# 0_Overview.net
KiCad netlist of a schematic drawn in Altium Designer
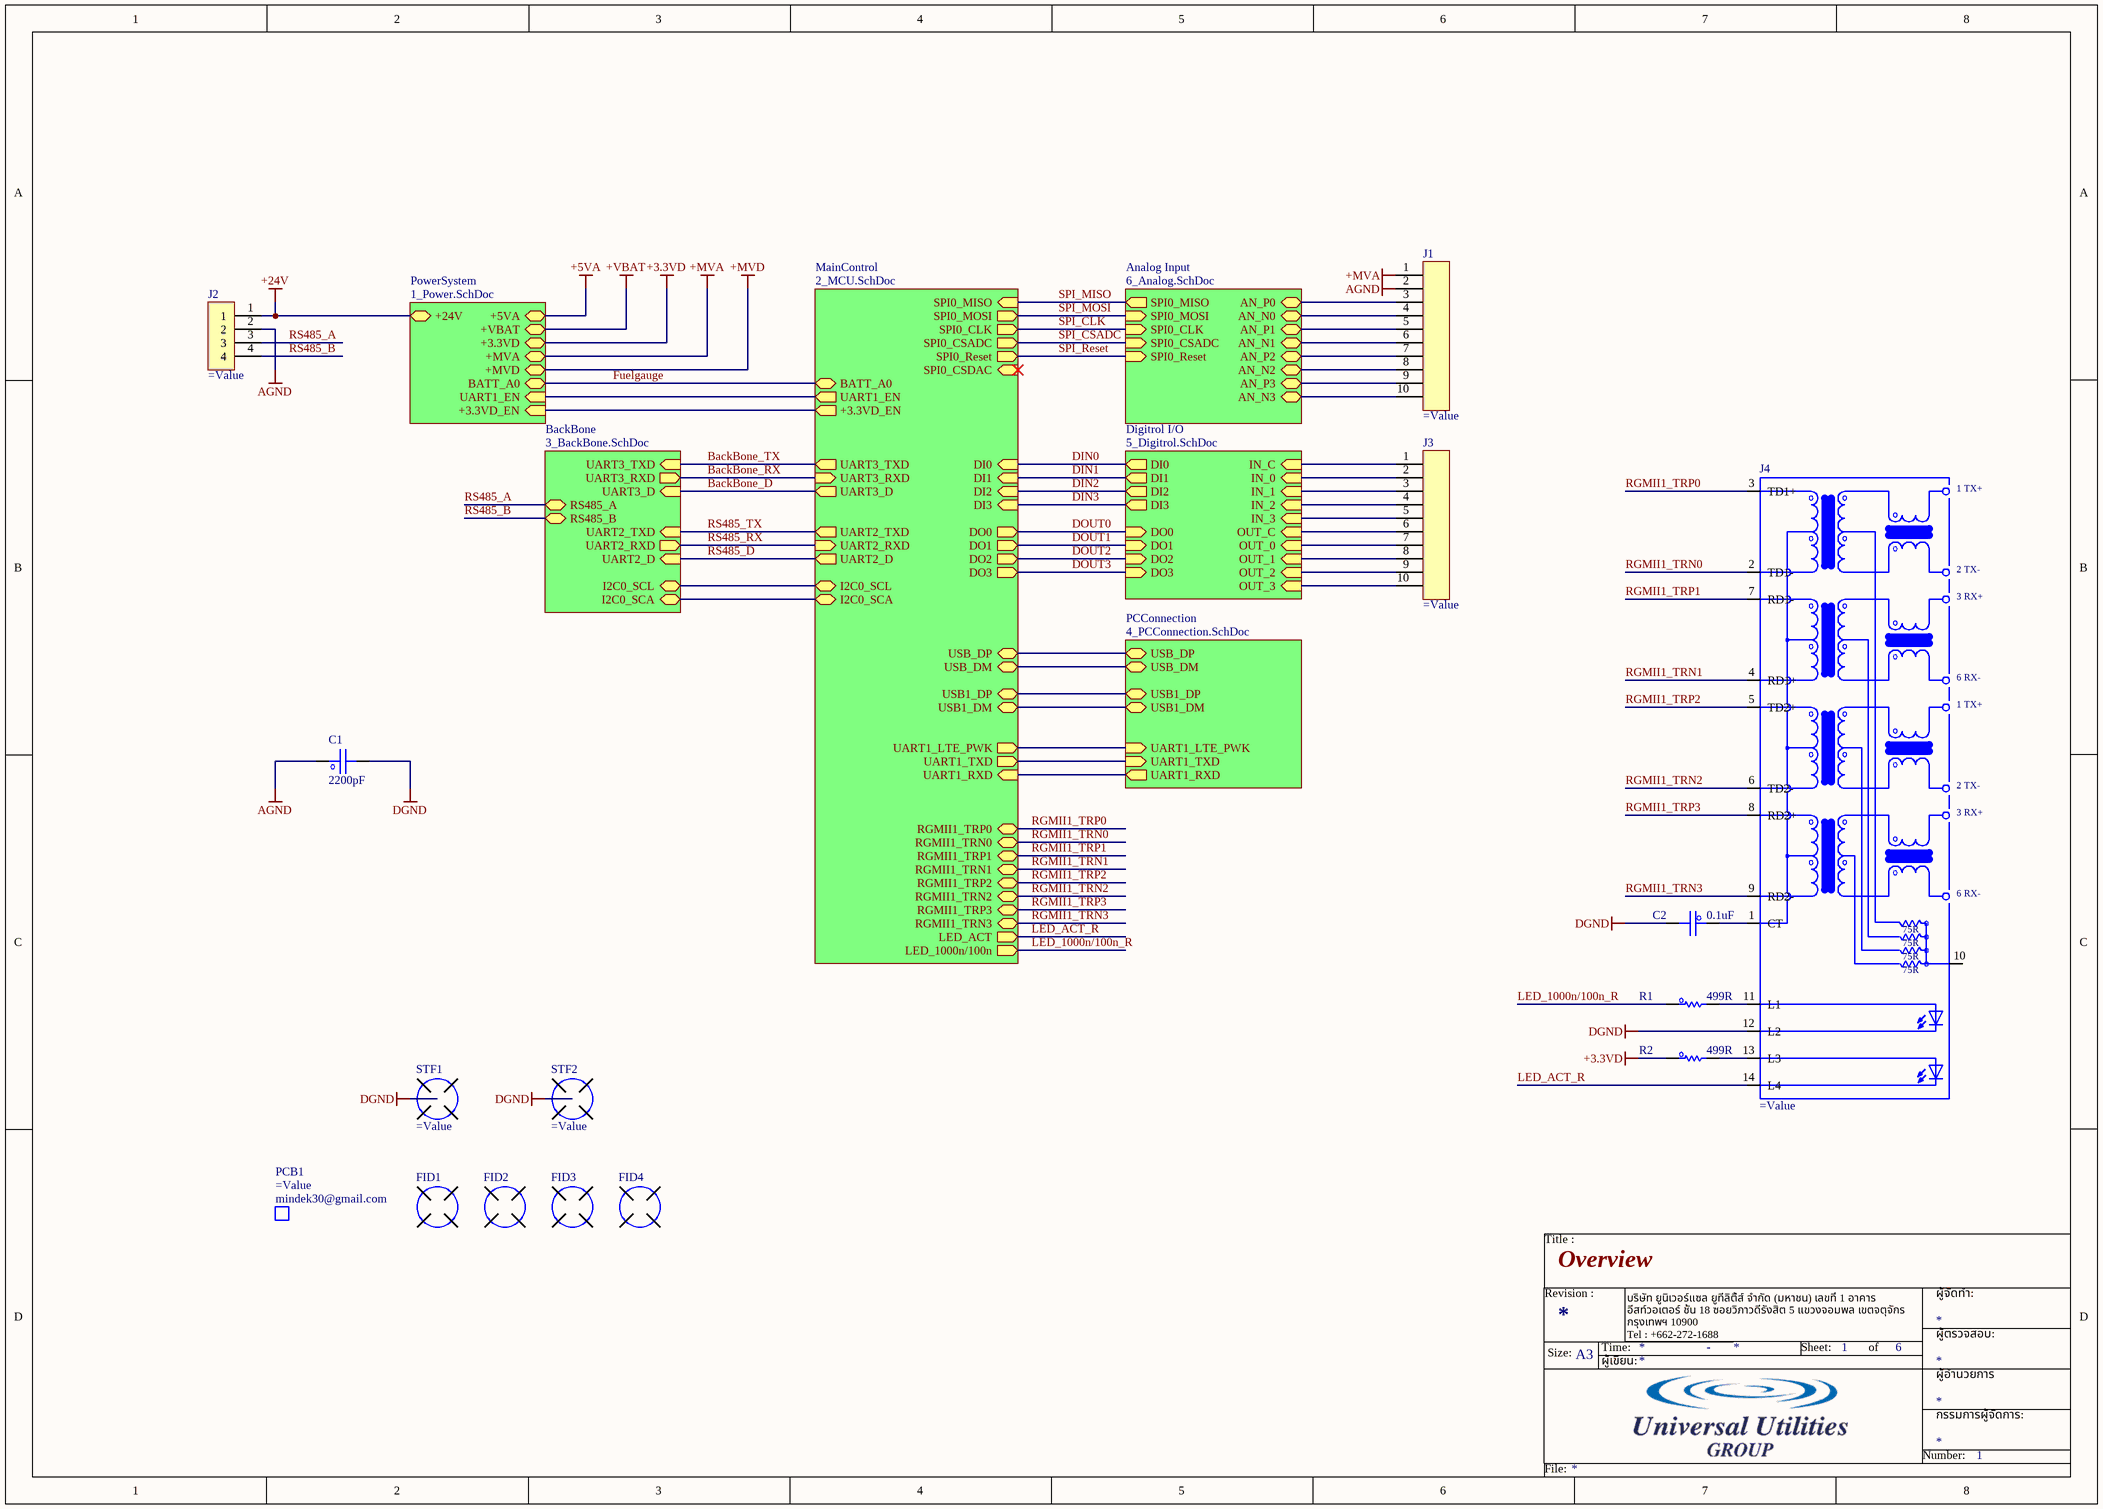
[diagram p0: 0_Overview.SchDoc]

(export (version "E")
  (design (tool "Eeschema 10.0.6"))
  (components
    (comp (ref "C1")
      (value "2200pF")
      (footprint "C_1206")
      (description "CAP CER 2200PF 1KV X7R 1206")
      (fields (field (name "MANUFACTURER") "AVX Corporation") (field (name "PARTNUMBER") "1206AC222KAT1A"))
      (libsource (lib "UUSymbol") (part "C_Capacitor"))
    )
    (comp (ref "C2")
      (value "0.1uF")
      (footprint "C_0603")
      (description "CAP CER 0.1UF 50V X7R 0603")
      (fields (field (name "MANUFACTURER") "KEMET") (field (name "PARTNUMBER") "C0603C104K5RACTU"))
      (libsource (lib "UUSymbol") (part "C_Capacitor"))
    )
    (comp (ref "FID1")
      (value "FIDUCIAL")
      (footprint "FID")
      (description "Fiducial")
      (fields (field (name "MANUFACTURER") "mindek30@gmail.com") (field (name "PARTNUMBER") "_"))
      (libsource (lib "UUSymbol") (part "FID_FIDUCIAL"))
    )
    (comp (ref "FID2")
      (value "FIDUCIAL")
      (footprint "FID")
      (description "Fiducial")
      (fields (field (name "MANUFACTURER") "mindek30@gmail.com") (field (name "PARTNUMBER") "_"))
      (libsource (lib "UUSymbol") (part "FID_FIDUCIAL"))
    )
    (comp (ref "FID3")
      (value "FIDUCIAL")
      (footprint "FID")
      (description "Fiducial")
      (fields (field (name "MANUFACTURER") "mindek30@gmail.com") (field (name "PARTNUMBER") "_"))
      (libsource (lib "UUSymbol") (part "FID_FIDUCIAL"))
    )
    (comp (ref "FID4")
      (value "FIDUCIAL")
      (footprint "FID")
      (description "Fiducial")
      (fields (field (name "MANUFACTURER") "mindek30@gmail.com") (field (name "PARTNUMBER") "_"))
      (libsource (lib "UUSymbol") (part "FID_FIDUCIAL"))
    )
    (comp (ref "J1")
      (value "~")
      (footprint "CON_10P_Terminal")
      (description "TERM BLOCK HDR 10POS 90DEG 3.5MM")
      (fields (field (name "PARTNUMBER") "1843871") (field (name "MANUFACTURER") "Phoenix Contact"))
      (libsource (lib "UUSymbol") (part "CON_10P_Terminal"))
    )
    (comp (ref "J2")
      (value "~")
      (footprint "CON_4P_Terminal")
      (description "TERM BLOCK HDR 4POS 90DEG 3.5MM")
      (fields (field (name "PARTNUMBER") "1843813") (field (name "MANUFACTURER") "Phoenix Contact"))
      (libsource (lib "UUSymbol") (part "CON_4P_Terminal"))
    )
    (comp (ref "J3")
      (value "~")
      (footprint "CON_10P_Terminal")
      (description "TERM BLOCK HDR 10POS 90DEG 3.5MM")
      (fields (field (name "PARTNUMBER") "1843871") (field (name "MANUFACTURER") "Phoenix Contact"))
      (libsource (lib "UUSymbol") (part "CON_10P_Terminal"))
    )
    (comp (ref "J4")
      (value "~")
      (footprint "HY911103A_HAN")
      (fields
        (field (name "PARTNUMBER") "HY911103A")
        (field (name "MANUFACTURER") "HANRUN(Zhongshan HanRun Elec)")
      )
      (libsource (lib "UUSymbol") (part "CON_RJ45_1"))
    )
    (comp (ref "PCB1")
      (value "~")
      (description "BARE PCB")
      (fields (field (name "MANUFACTURER") "mindek30@gmail.com") (field (name "PARTNUMBER") "_"))
      (libsource (lib "UUSymbol") (part "PCB_Bare"))
    )
    (comp (ref "R1")
      (value "499R")
      (footprint "R_0603")
      (description "RES 499 OHM 1% 1/10W 0603")
      (fields (field (name "MANUFACTURER") "Vishay Dale") (field (name "PARTNUMBER") "CRCW0603499RFKEAC"))
      (libsource (lib "UUSymbol") (part "R_Resister"))
    )
    (comp (ref "R2")
      (value "499R")
      (footprint "R_0603")
      (description "RES 499 OHM 1% 1/10W 0603")
      (fields (field (name "MANUFACTURER") "Vishay Dale") (field (name "PARTNUMBER") "CRCW0603499RFKEAC"))
      (libsource (lib "UUSymbol") (part "R_Resister"))
    )
    (comp (ref "STF1")
      (value "~")
      (footprint "StandOff")
      (description "ROUND STANDOFF M2X0.4 STEEL 2MM")
      (fields (field (name "MANUFACTURER") "Würth Elektronik") (field (name "PARTNUMBER") "9774020243R"))
      (libsource (lib "UUSymbol") (part "FID_STANDOFF"))
    )
    (comp (ref "STF2")
      (value "~")
      (footprint "StandOff")
      (description "ROUND STANDOFF M2X0.4 STEEL 2MM")
      (fields (field (name "MANUFACTURER") "Würth Elektronik") (field (name "PARTNUMBER") "9774020243R"))
      (libsource (lib "UUSymbol") (part "FID_STANDOFF"))
    )
  )
  (nets
    (net (code "1") (name "+3.3VD") (class "Default")
      (node (ref "R2") (pin "1") (pinfunction "1_1") (pintype "passive"))
    )
    (net (code "3") (name "+24V") (class "Default")
      (node (ref "J2") (pin "1") (pinfunction "1_1") (pintype "passive"))
    )
    (net (code "4") (name "+MVA") (class "Default")
      (node (ref "J1") (pin "1") (pinfunction "1_1") (pintype "passive"))
    )
    (net (code "8") (name "/AN_N0") (class "Default")
      (node (ref "J1") (pin "4") (pinfunction "4_4") (pintype "passive"))
    )
    (net (code "9") (name "/AN_N1") (class "Default")
      (node (ref "J1") (pin "6") (pinfunction "6_6") (pintype "passive"))
    )
    (net (code "10") (name "/AN_N2") (class "Default")
      (node (ref "J1") (pin "8") (pinfunction "8_8") (pintype "passive"))
    )
    (net (code "11") (name "/AN_N3") (class "Default")
      (node (ref "J1") (pin "10") (pinfunction "10_10") (pintype "passive"))
    )
    (net (code "12") (name "/AN_P0") (class "Default")
      (node (ref "J1") (pin "3") (pinfunction "3_3") (pintype "passive"))
    )
    (net (code "13") (name "/AN_P1") (class "Default")
      (node (ref "J1") (pin "5") (pinfunction "5_5") (pintype "passive"))
    )
    (net (code "14") (name "/AN_P2") (class "Default")
      (node (ref "J1") (pin "7") (pinfunction "7_7") (pintype "passive"))
    )
    (net (code "15") (name "/AN_P3") (class "Default")
      (node (ref "J1") (pin "9") (pinfunction "9_9") (pintype "passive"))
    )
    (net (code "30") (name "/IN_0") (class "Default")
      (node (ref "J3") (pin "2") (pinfunction "2_2") (pintype "passive"))
    )
    (net (code "31") (name "/IN_1") (class "Default")
      (node (ref "J3") (pin "3") (pinfunction "3_3") (pintype "passive"))
    )
    (net (code "32") (name "/IN_2") (class "Default")
      (node (ref "J3") (pin "4") (pinfunction "4_4") (pintype "passive"))
    )
    (net (code "33") (name "/IN_3") (class "Default")
      (node (ref "J3") (pin "5") (pinfunction "5_5") (pintype "passive"))
    )
    (net (code "34") (name "/IN_C") (class "Default")
      (node (ref "J3") (pin "1") (pinfunction "1_1") (pintype "passive"))
    )
    (net (code "35") (name "/LED_1000n{slash}100n_R") (class "Default")
      (node (ref "R1") (pin "1") (pinfunction "1_1") (pintype "passive"))
    )
    (net (code "36") (name "/LED_ACT_R") (class "Default")
      (node (ref "J4") (pin "14") (pinfunction "L4_14") (pintype "passive"))
    )
    (net (code "37") (name "/OUT_0") (class "Default")
      (node (ref "J3") (pin "7") (pinfunction "7_7") (pintype "passive"))
    )
    (net (code "38") (name "/OUT_1") (class "Default")
      (node (ref "J3") (pin "8") (pinfunction "8_8") (pintype "passive"))
    )
    (net (code "39") (name "/OUT_2") (class "Default")
      (node (ref "J3") (pin "9") (pinfunction "9_9") (pintype "passive"))
    )
    (net (code "40") (name "/OUT_3") (class "Default")
      (node (ref "J3") (pin "10") (pinfunction "10_10") (pintype "passive"))
    )
    (net (code "41") (name "/OUT_C") (class "Default")
      (node (ref "J3") (pin "6") (pinfunction "6_6") (pintype "passive"))
    )
    (net (code "42") (name "/RGMII1_TRN0") (class "Default")
      (node (ref "J4") (pin "2") (pinfunction "TD1-_2") (pintype "passive"))
    )
    (net (code "43") (name "/RGMII1_TRN1") (class "Default")
      (node (ref "J4") (pin "4") (pinfunction "RD1+_4") (pintype "passive"))
    )
    (net (code "44") (name "/RGMII1_TRN2") (class "Default")
      (node (ref "J4") (pin "6") (pinfunction "TD2-_6") (pintype "passive"))
    )
    (net (code "45") (name "/RGMII1_TRN3") (class "Default")
      (node (ref "J4") (pin "9") (pinfunction "RD2-_9") (pintype "passive"))
    )
    (net (code "46") (name "/RGMII1_TRP0") (class "Default")
      (node (ref "J4") (pin "3") (pinfunction "TD1+_3") (pintype "passive"))
    )
    (net (code "47") (name "/RGMII1_TRP1") (class "Default")
      (node (ref "J4") (pin "7") (pinfunction "RD1-_7") (pintype "passive"))
    )
    (net (code "48") (name "/RGMII1_TRP2") (class "Default")
      (node (ref "J4") (pin "5") (pinfunction "TD2+_5") (pintype "passive"))
    )
    (net (code "49") (name "/RGMII1_TRP3") (class "Default")
      (node (ref "J4") (pin "8") (pinfunction "RD2+_8") (pintype "passive"))
    )
    (net (code "50") (name "/RS485_A") (class "Default")
      (node (ref "J2") (pin "3") (pinfunction "3_3") (pintype "passive"))
    )
    (net (code "51") (name "/RS485_B") (class "Default")
      (node (ref "J2") (pin "4") (pinfunction "4_4") (pintype "passive"))
    )
    (net (code "69") (name "AGND") (class "Default")
      (node (ref "C1") (pin "1") (pinfunction "1_1") (pintype "passive"))
      (node (ref "J1") (pin "2") (pinfunction "2_2") (pintype "passive"))
      (node (ref "J2") (pin "2") (pinfunction "2_2") (pintype "passive"))
    )
    (net (code "70") (name "DGND") (class "Default")
      (node (ref "C1") (pin "2") (pinfunction "2_2") (pintype "passive"))
      (node (ref "C2") (pin "2") (pinfunction "2_2") (pintype "passive"))
      (node (ref "J4") (pin "12") (pinfunction "L2_12") (pintype "passive"))
      (node (ref "STF1") (pin "1") (pinfunction "1_1") (pintype "passive"))
      (node (ref "STF2") (pin "1") (pinfunction "1_1") (pintype "passive"))
    )
    (net (code "71") (name "Net-(C2-Pad1)") (class "Default")
      (node (ref "C2") (pin "1") (pinfunction "1_1") (pintype "passive"))
      (node (ref "J4") (pin "1") (pinfunction "CT_1") (pintype "passive"))
    )
    (net (code "72") (name "Net-(J4-L1)") (class "Default")
      (node (ref "J4") (pin "11") (pinfunction "L1_11") (pintype "passive"))
      (node (ref "R1") (pin "2") (pinfunction "2_2") (pintype "passive"))
    )
    (net (code "73") (name "Net-(J4-L3)") (class "Default")
      (node (ref "J4") (pin "13") (pinfunction "L3_13") (pintype "passive"))
      (node (ref "R2") (pin "2") (pinfunction "2_2") (pintype "passive"))
    )
    (net (code "74") (name "unconnected-(J4-CT-Pad10)") (class "Default")
      (node (ref "J4") (pin "10") (pinfunction "CT_10") (pintype "passive"))
    )
  )
)
